# Boost.net
KiCad netlist of a schematic drawn in Altium Designer
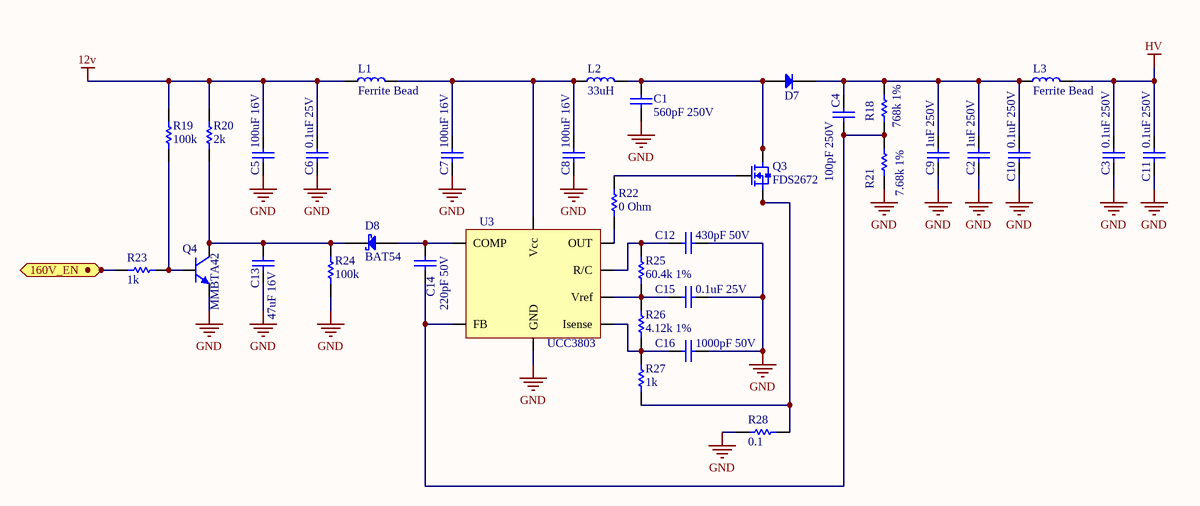
[diagram p0: Boost.SchDoc]

(export (version "E")
  (design (tool "Eeschema 10.0.6"))
  (components
    (comp (ref "C1")
      (value "560pF 250V")
      (footprint "C0603")
      (description "CAP CER 560PF 250V C0G/NP0 0603")
      (libsource (lib "Schlib1") (part "560pF 250V 0603"))
    )
    (comp (ref "C2")
      (value "1uF 250V")
      (footprint "C2220")
      (description "CAP CER 1UF 250V X7R 2220")
      (libsource (lib "Schlib1") (part "1uF 250V 2220"))
    )
    (comp (ref "C3")
      (value "0.1uF 250V")
      (footprint "C0805")
      (description "CAP CER 0.1UF 250V X7T 0805")
      (libsource (lib "Schlib1") (part "0.1uF 250V 0805"))
    )
    (comp (ref "C4")
      (value "100pF 250V")
      (footprint "C0805")
      (description "CAP CER 100PF 250V C0G/NP0 0805")
      (libsource (lib "Schlib1") (part "100pF 250V 0805"))
    )
    (comp (ref "C5")
      (value "100uF 16V")
      (footprint "C1210")
      (description "CAP CER 100UF 16V X5R 1210")
      (libsource (lib "Schlib1") (part "100uF 16V 1210"))
    )
    (comp (ref "C6")
      (value "0.1uF 25V")
      (footprint "C0805")
      (description "CAP CER 0.1UF 25V Y5V 0805")
      (libsource (lib "Schlib1") (part "0.1uF 25V 0805"))
    )
    (comp (ref "C7")
      (value "100uF 16V")
      (footprint "C1210")
      (description "CAP CER 100UF 16V X5R 1210")
      (libsource (lib "Schlib1") (part "100uF 16V 1210"))
    )
    (comp (ref "C8")
      (value "100uF 16V")
      (footprint "C1210")
      (description "CAP CER 100UF 16V X5R 1210")
      (libsource (lib "Schlib1") (part "100uF 16V 1210"))
    )
    (comp (ref "C9")
      (value "1uF 250V")
      (footprint "C2220")
      (description "CAP CER 1UF 250V X7R 2220")
      (libsource (lib "Schlib1") (part "1uF 250V 2220"))
    )
    (comp (ref "C10")
      (value "0.1uF 250V")
      (footprint "C0805")
      (description "CAP CER 0.1UF 250V X7T 0805")
      (libsource (lib "Schlib1") (part "0.1uF 250V 0805"))
    )
    (comp (ref "C11")
      (value "0.1uF 250V")
      (footprint "C0805")
      (description "CAP CER 0.1UF 250V X7T 0805")
      (libsource (lib "Schlib1") (part "0.1uF 250V 0805"))
    )
    (comp (ref "C12")
      (value "430pF 50V")
      (footprint "C0805")
      (description "CAP CER 430PF 50V C0G/NP0 0805")
      (libsource (lib "Schlib1") (part "430pF 50V 0805"))
    )
    (comp (ref "C13")
      (value "47uF 16V")
      (footprint "C1206")
      (description "CAP CER 47UF 16V JB 1206")
      (libsource (lib "Schlib1") (part "47uF 16V 1206"))
    )
    (comp (ref "C14")
      (value "220pF 50V")
      (footprint "C0805")
      (description "CAP CER 220PF 50V X7R 0805")
      (libsource (lib "Schlib1") (part "220pF 50V 0805"))
    )
    (comp (ref "C15")
      (value "0.1uF 25V")
      (footprint "C0805")
      (description "CAP CER 0.1UF 25V Y5V 0805")
      (libsource (lib "Schlib1") (part "0.1uF 25V 0805"))
    )
    (comp (ref "C16")
      (value "1000pF 50V")
      (footprint "C0805")
      (description "CAP CER 1000PF 50V X7R 0805")
      (libsource (lib "Schlib1") (part "1000pF 50V 0805"))
    )
    (comp (ref "D7")
      (value "Diode")
      (footprint "SMA")
      (description "DIODE GEN PURP 200V 1A SMA")
      (libsource (lib "Schlib1") (part "Diode 200V 1A"))
    )
    (comp (ref "D8")
      (value "BAT54")
      (footprint "SOD-323")
      (description "DIODE BAT54 SCHOTTKY 30V 100MA SOD323")
      (libsource (lib "Schlib1") (part "Diode 30V 100mA"))
    )
    (comp (ref "L1")
      (value "Ferrite Bead")
      (footprint "R0805")
      (description "FERRITE BEAD 60 OHM 0805 1LN")
      (libsource (lib "Schlib1") (part "Ferrite Bead 60 Ohm"))
    )
    (comp (ref "L2")
      (value "33uH")
      (footprint "Wurth 7447709330")
      (description "FIXED IND 33UH 4.2A 45 MOHM SMD")
      (libsource (lib "Schlib1") (part "33uH"))
    )
    (comp (ref "L3")
      (value "Ferrite Bead")
      (footprint "R0805")
      (description "FERRITE BEAD 60 OHM 0805 1LN")
      (libsource (lib "Schlib1") (part "Ferrite Bead 60 Ohm"))
    )
    (comp (ref "Q3")
      (value "FDS2672")
      (footprint "8-SOIC")
      (description "MOSFET N-CH 200V 3.9A 8-SOIC")
      (libsource (lib "Schlib1") (part "N-FET FDS2672"))
    )
    (comp (ref "Q4")
      (value "MMBTA42")
      (footprint "SOT_23")
      (description "TRANS MMBTA42 NPN 300V 0.3A SOT23")
      (libsource (lib "Schlib1") (part "NPN 300V 0.3A"))
    )
    (comp (ref "R18")
      (value "768k 1%")
      (footprint "R0805")
      (description "RES SMD 768K OHM 1% 1/8W 0805")
      (libsource (lib "Schlib1") (part "768k 0805 1%"))
    )
    (comp (ref "R19")
      (value "100k")
      (footprint "R0603")
      (description "RES SMD 100K OHM 5% 1/10W 0603")
      (libsource (lib "Schlib1") (part "100k 0603 5%"))
    )
    (comp (ref "R20")
      (value "2k")
      (footprint "R0805")
      (description "RES SMD 2K OHM 5% 1/8W 0805")
      (libsource (lib "Schlib1") (part "2k 0805 5%"))
    )
    (comp (ref "R21")
      (value "7.68k 1%")
      (footprint "R0805")
      (description "RES SMD 7.68K OHM 1% 1/8W 0805")
      (libsource (lib "Schlib1") (part "7.68k 0805 1%"))
    )
    (comp (ref "R22")
      (value "0 Ohm")
      (footprint "R0805")
      (description "RES SMD 0 OHM JUMPER 1/8W 0805")
      (libsource (lib "Schlib1") (part "0 Ohm 0805"))
    )
    (comp (ref "R23")
      (value "1k")
      (footprint "R0805")
      (description "RES SMD 1K OHM 5% 1/8W 0805")
      (libsource (lib "Schlib1") (part "1k 0805 5%"))
    )
    (comp (ref "R24")
      (value "100k")
      (footprint "R0603")
      (description "RES SMD 100K OHM 5% 1/10W 0603")
      (libsource (lib "Schlib1") (part "100k 0603 5%"))
    )
    (comp (ref "R25")
      (value "60.4k 1%")
      (footprint "R0805")
      (description "RES SMD 60.4K OHM 1% 1/8W 0805")
      (libsource (lib "Schlib1") (part "60.4k 0805 1%"))
    )
    (comp (ref "R26")
      (value "4.12k 1%")
      (footprint "R0805")
      (description "RES SMD 4.12K OHM 1% 1/8W 0805")
      (libsource (lib "Schlib1") (part "4.12k 0805 1%"))
    )
    (comp (ref "R27")
      (value "1k")
      (footprint "R0805")
      (description "RES SMD 1K OHM 5% 1/8W 0805")
      (libsource (lib "Schlib1") (part "1k 0805 5%"))
    )
    (comp (ref "R28")
      (value "0.1")
      (footprint "R0805")
      (description "RES 0.1 OHM 1% 1/2W 0805")
      (libsource (lib "Schlib1") (part "0.1 0805 1%"))
    )
    (comp (ref "U3")
      (value "UCC3803")
      (footprint "8-SOIC")
      (description "IC REG CTRLR MULT TOPOLOGY 8SOIC")
      (libsource (lib "Schlib1") (part "UCC3803DTR"))
    )
  )
  (nets
    (net (code "1") (name "/160V_EN") (class "Default")
      (node (ref "R23") (pin "1") (pinfunction "1_1") (pintype "passive"))
    )
    (net (code "2") (name "12v") (class "Default")
      (node (ref "C5") (pin "2") (pinfunction "2_2") (pintype "passive"))
      (node (ref "C6") (pin "2") (pinfunction "2_2") (pintype "passive"))
      (node (ref "L1") (pin "1") (pinfunction "1_1") (pintype "passive"))
      (node (ref "R19") (pin "2") (pinfunction "2_2") (pintype "passive"))
      (node (ref "R20") (pin "2") (pinfunction "2_2") (pintype "passive"))
    )
    (net (code "3") (name "GND") (class "Default")
      (node (ref "C1") (pin "1") (pinfunction "1_1") (pintype "passive"))
      (node (ref "C10") (pin "1") (pinfunction "1_1") (pintype "passive"))
      (node (ref "C11") (pin "1") (pinfunction "1_1") (pintype "passive"))
      (node (ref "C12") (pin "2") (pinfunction "2_2") (pintype "passive"))
      (node (ref "C13") (pin "1") (pinfunction "1_1") (pintype "passive"))
      (node (ref "C15") (pin "2") (pinfunction "2_2") (pintype "passive"))
      (node (ref "C16") (pin "1") (pinfunction "1_1") (pintype "passive"))
      (node (ref "C2") (pin "1") (pinfunction "1_1") (pintype "passive"))
      (node (ref "C3") (pin "1") (pinfunction "1_1") (pintype "passive"))
      (node (ref "C5") (pin "1") (pinfunction "1_1") (pintype "passive"))
      (node (ref "C6") (pin "1") (pinfunction "1_1") (pintype "passive"))
      (node (ref "C7") (pin "1") (pinfunction "1_1") (pintype "passive"))
      (node (ref "C8") (pin "1") (pinfunction "1_1") (pintype "passive"))
      (node (ref "C9") (pin "1") (pinfunction "1_1") (pintype "passive"))
      (node (ref "Q4") (pin "3") (pinfunction "E_3") (pintype "passive"))
      (node (ref "R21") (pin "1") (pinfunction "1_1") (pintype "passive"))
      (node (ref "R24") (pin "1") (pinfunction "1_1") (pintype "passive"))
      (node (ref "R28") (pin "1") (pinfunction "1_1") (pintype "passive"))
      (node (ref "U3") (pin "5") (pinfunction "GND_5") (pintype "passive"))
    )
    (net (code "4") (name "HV") (class "Default")
      (node (ref "C11") (pin "2") (pinfunction "2_2") (pintype "passive"))
      (node (ref "C3") (pin "2") (pinfunction "2_2") (pintype "passive"))
      (node (ref "L3") (pin "2") (pinfunction "2_2") (pintype "passive"))
    )
    (net (code "5") (name "Net-(D7-A)") (class "Default")
      (node (ref "C1") (pin "2") (pinfunction "2_2") (pintype "passive"))
      (node (ref "D7") (pin "1") (pinfunction "A_1") (pintype "passive"))
      (node (ref "L2") (pin "2") (pinfunction "2_2") (pintype "passive"))
      (node (ref "Q3") (pin "5") (pinfunction "5_5") (pintype "passive"))
      (node (ref "Q3") (pin "6") (pinfunction "6_6") (pintype "passive"))
      (node (ref "Q3") (pin "7") (pinfunction "7_7") (pintype "passive"))
      (node (ref "Q3") (pin "8") (pinfunction "8_8") (pintype "passive"))
    )
    (net (code "6") (name "Net-(D7-K)") (class "Default")
      (node (ref "C10") (pin "2") (pinfunction "2_2") (pintype "passive"))
      (node (ref "C2") (pin "2") (pinfunction "2_2") (pintype "passive"))
      (node (ref "C4") (pin "2") (pinfunction "2_2") (pintype "passive"))
      (node (ref "C9") (pin "2") (pinfunction "2_2") (pintype "passive"))
      (node (ref "D7") (pin "2") (pinfunction "K_2") (pintype "passive"))
      (node (ref "L3") (pin "1") (pinfunction "1_1") (pintype "passive"))
      (node (ref "R18") (pin "2") (pinfunction "2_2") (pintype "passive"))
    )
    (net (code "7") (name "Net-(D8-A)") (class "Default")
      (node (ref "C14") (pin "2") (pinfunction "2_2") (pintype "passive"))
      (node (ref "D8") (pin "1") (pinfunction "A_1") (pintype "passive"))
      (node (ref "U3") (pin "1") (pinfunction "COMP_1") (pintype "passive"))
    )
    (net (code "8") (name "Net-(D8-K)") (class "Default")
      (node (ref "C13") (pin "2") (pinfunction "2_2") (pintype "passive"))
      (node (ref "D8") (pin "2") (pinfunction "K_2") (pintype "passive"))
      (node (ref "Q4") (pin "1") (pinfunction "C_1") (pintype "passive"))
      (node (ref "R20") (pin "1") (pinfunction "1_1") (pintype "passive"))
      (node (ref "R24") (pin "2") (pinfunction "2_2") (pintype "passive"))
    )
    (net (code "9") (name "Net-(Q3-Pad1)") (class "Default")
      (node (ref "Q3") (pin "1") (pinfunction "1_1") (pintype "passive"))
      (node (ref "Q3") (pin "2") (pinfunction "2_2") (pintype "passive"))
      (node (ref "Q3") (pin "3") (pinfunction "3_3") (pintype "passive"))
      (node (ref "R27") (pin "2") (pinfunction "2_2") (pintype "passive"))
      (node (ref "R28") (pin "2") (pinfunction "2_2") (pintype "passive"))
    )
    (net (code "10") (name "Net-(Q3-Pad4)") (class "Default")
      (node (ref "Q3") (pin "4") (pinfunction "4_4") (pintype "passive"))
      (node (ref "R22") (pin "2") (pinfunction "2_2") (pintype "passive"))
    )
    (net (code "11") (name "Net-(Q4-B)") (class "Default")
      (node (ref "Q4") (pin "2") (pinfunction "B_2") (pintype "passive"))
      (node (ref "R19") (pin "1") (pinfunction "1_1") (pintype "passive"))
      (node (ref "R23") (pin "2") (pinfunction "2_2") (pintype "passive"))
    )
    (net (code "12") (name "Net-(U3-FB)") (class "Default")
      (node (ref "C14") (pin "1") (pinfunction "1_1") (pintype "passive"))
      (node (ref "C4") (pin "1") (pinfunction "1_1") (pintype "passive"))
      (node (ref "R18") (pin "1") (pinfunction "1_1") (pintype "passive"))
      (node (ref "R21") (pin "2") (pinfunction "2_2") (pintype "passive"))
      (node (ref "U3") (pin "2") (pinfunction "FB_2") (pintype "passive"))
    )
    (net (code "13") (name "Net-(U3-Isense)") (class "Default")
      (node (ref "C16") (pin "2") (pinfunction "2_2") (pintype "passive"))
      (node (ref "R26") (pin "2") (pinfunction "2_2") (pintype "passive"))
      (node (ref "R27") (pin "1") (pinfunction "1_1") (pintype "passive"))
      (node (ref "U3") (pin "3") (pinfunction "Isense_3") (pintype "passive"))
    )
    (net (code "14") (name "Net-(U3-OUT)") (class "Default")
      (node (ref "R22") (pin "1") (pinfunction "1_1") (pintype "passive"))
      (node (ref "U3") (pin "6") (pinfunction "OUT_6") (pintype "passive"))
    )
    (net (code "15") (name "Net-(U3-R{slash}C)") (class "Default")
      (node (ref "C12") (pin "1") (pinfunction "1_1") (pintype "passive"))
      (node (ref "R25") (pin "1") (pinfunction "1_1") (pintype "passive"))
      (node (ref "U3") (pin "4") (pinfunction "R/C_4") (pintype "passive"))
    )
    (net (code "16") (name "Net-(U3-Vcc)") (class "Default")
      (node (ref "C7") (pin "2") (pinfunction "2_2") (pintype "passive"))
      (node (ref "C8") (pin "2") (pinfunction "2_2") (pintype "passive"))
      (node (ref "L1") (pin "2") (pinfunction "2_2") (pintype "passive"))
      (node (ref "L2") (pin "1") (pinfunction "1_1") (pintype "passive"))
      (node (ref "U3") (pin "7") (pinfunction "Vcc_7") (pintype "passive"))
    )
    (net (code "17") (name "Net-(U3-Vref)") (class "Default")
      (node (ref "C15") (pin "1") (pinfunction "1_1") (pintype "passive"))
      (node (ref "R25") (pin "2") (pinfunction "2_2") (pintype "passive"))
      (node (ref "R26") (pin "1") (pinfunction "1_1") (pintype "passive"))
      (node (ref "U3") (pin "8") (pinfunction "Vref_8") (pintype "passive"))
    )
  )
)
